# rgb-controller.net
KiCad netlist of a schematic drawn in EAGLE
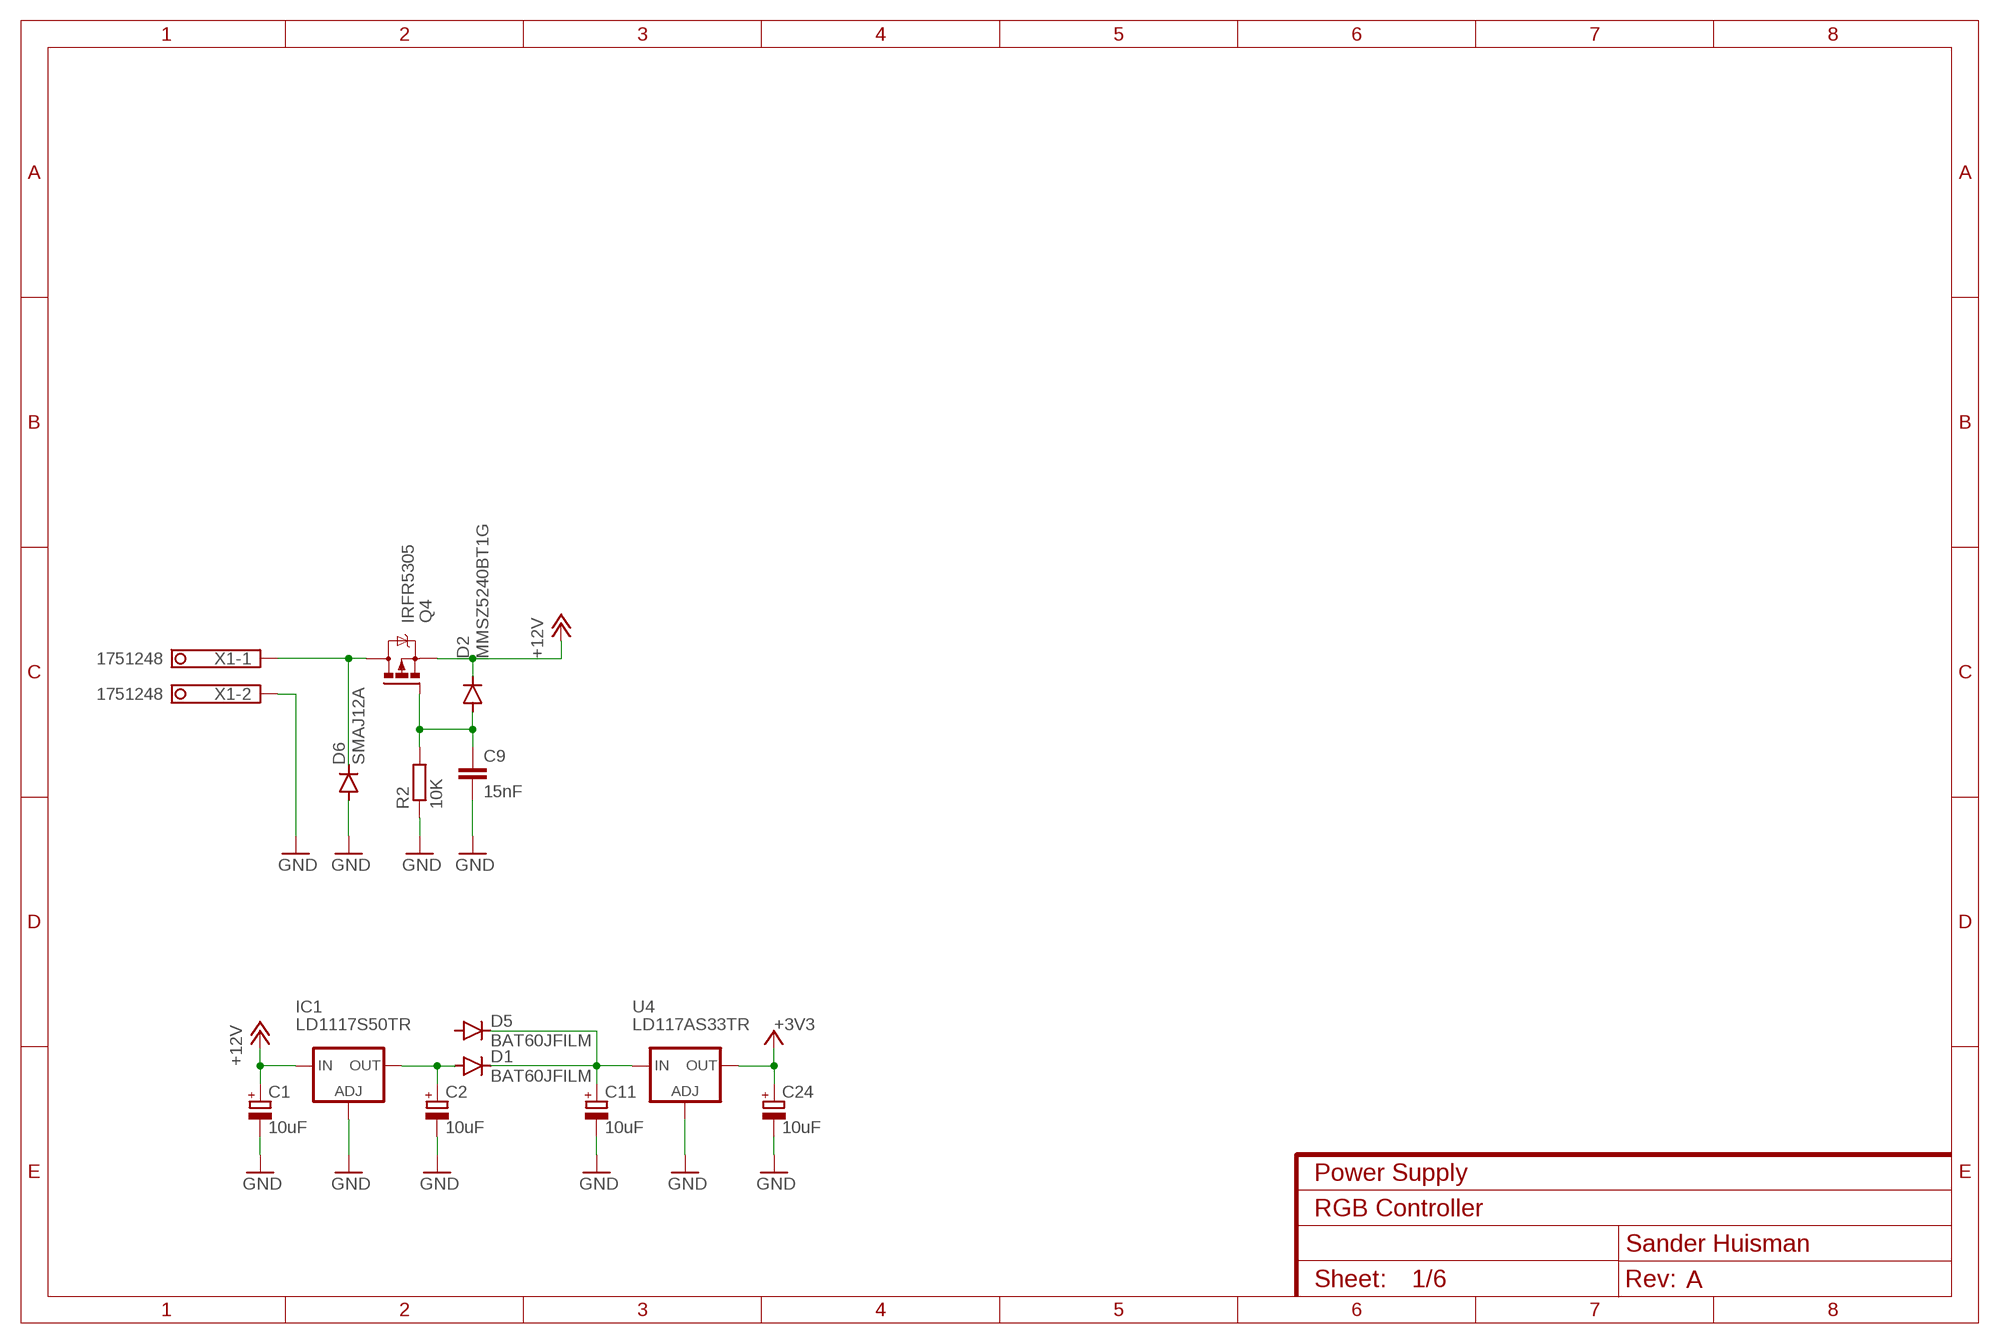
[diagram p0: schematic, sheet 1]
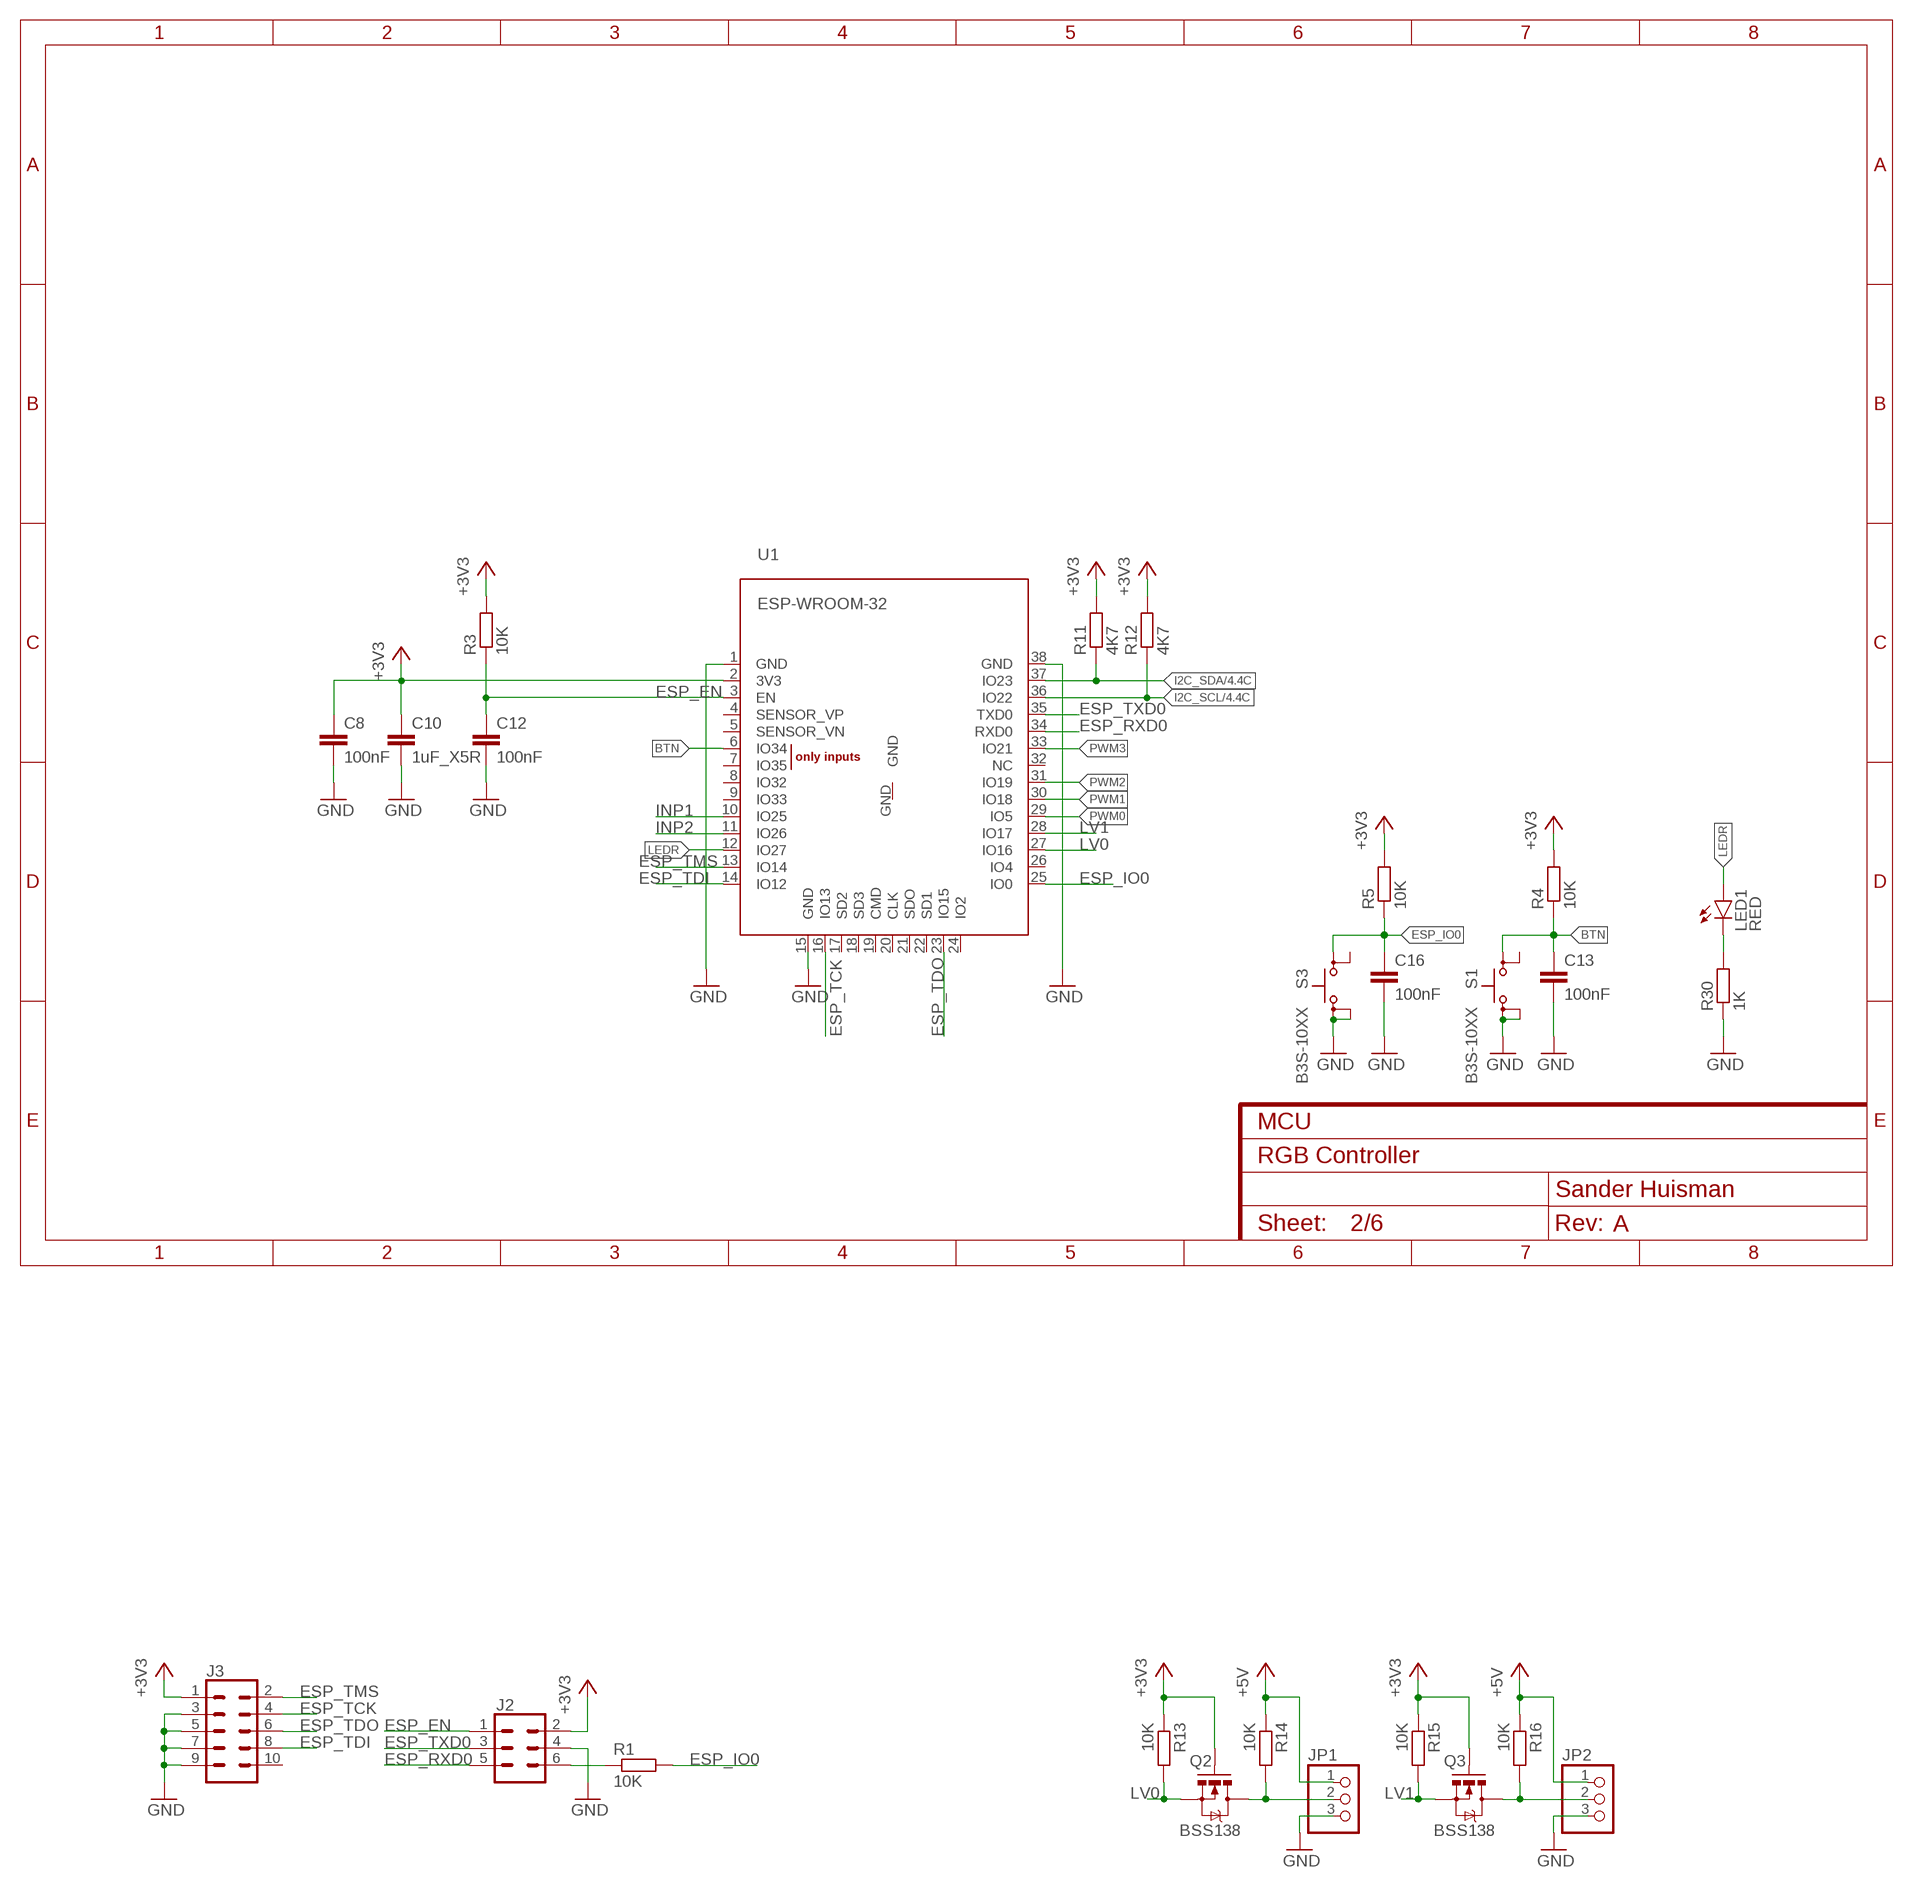
[diagram p1: schematic, sheet 2]
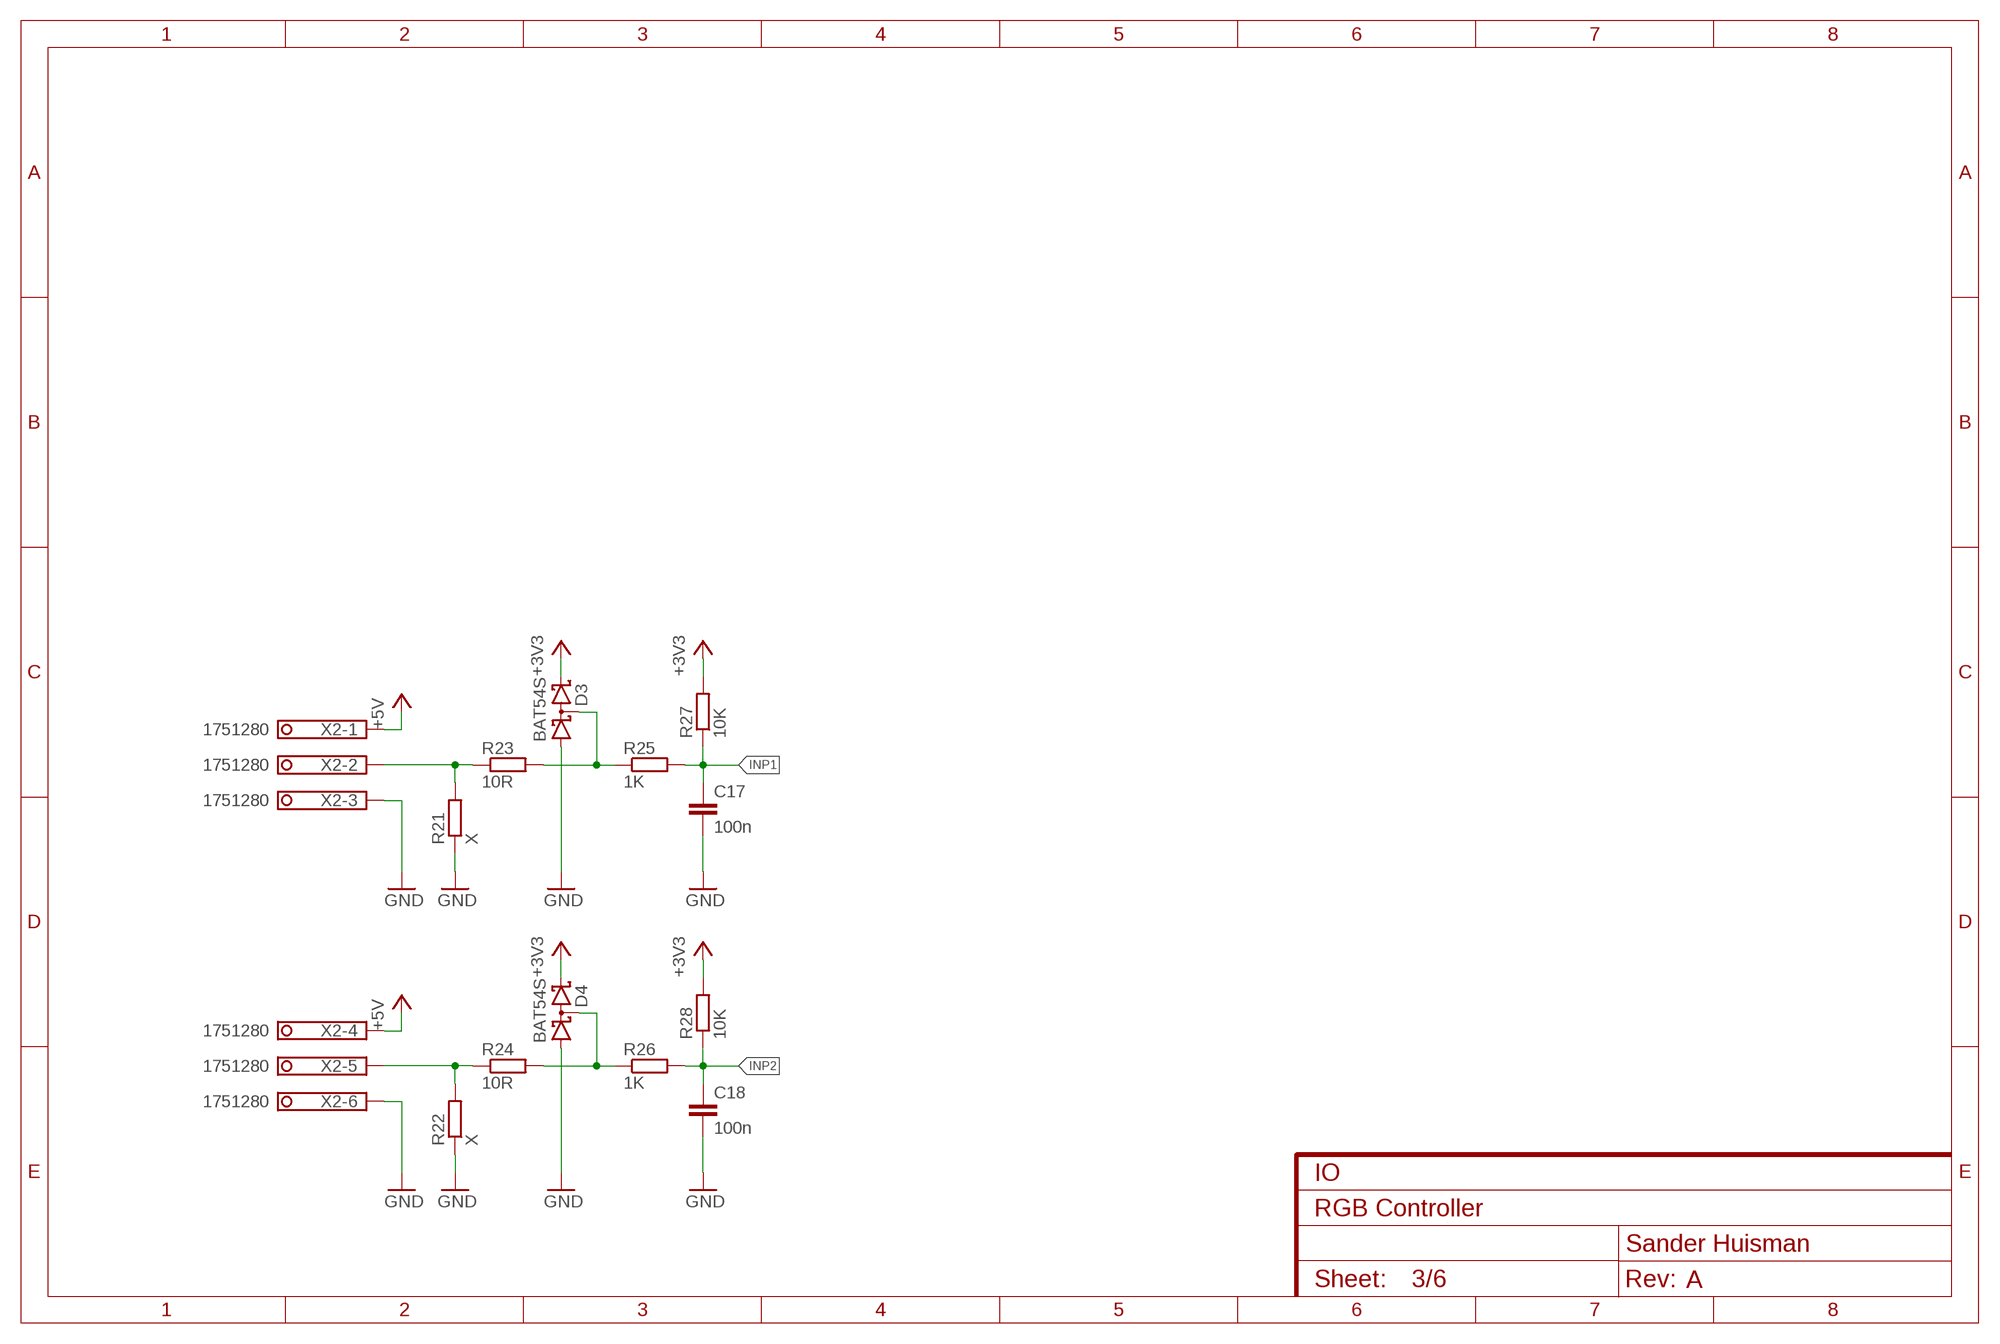
[diagram p2: schematic, sheet 3]
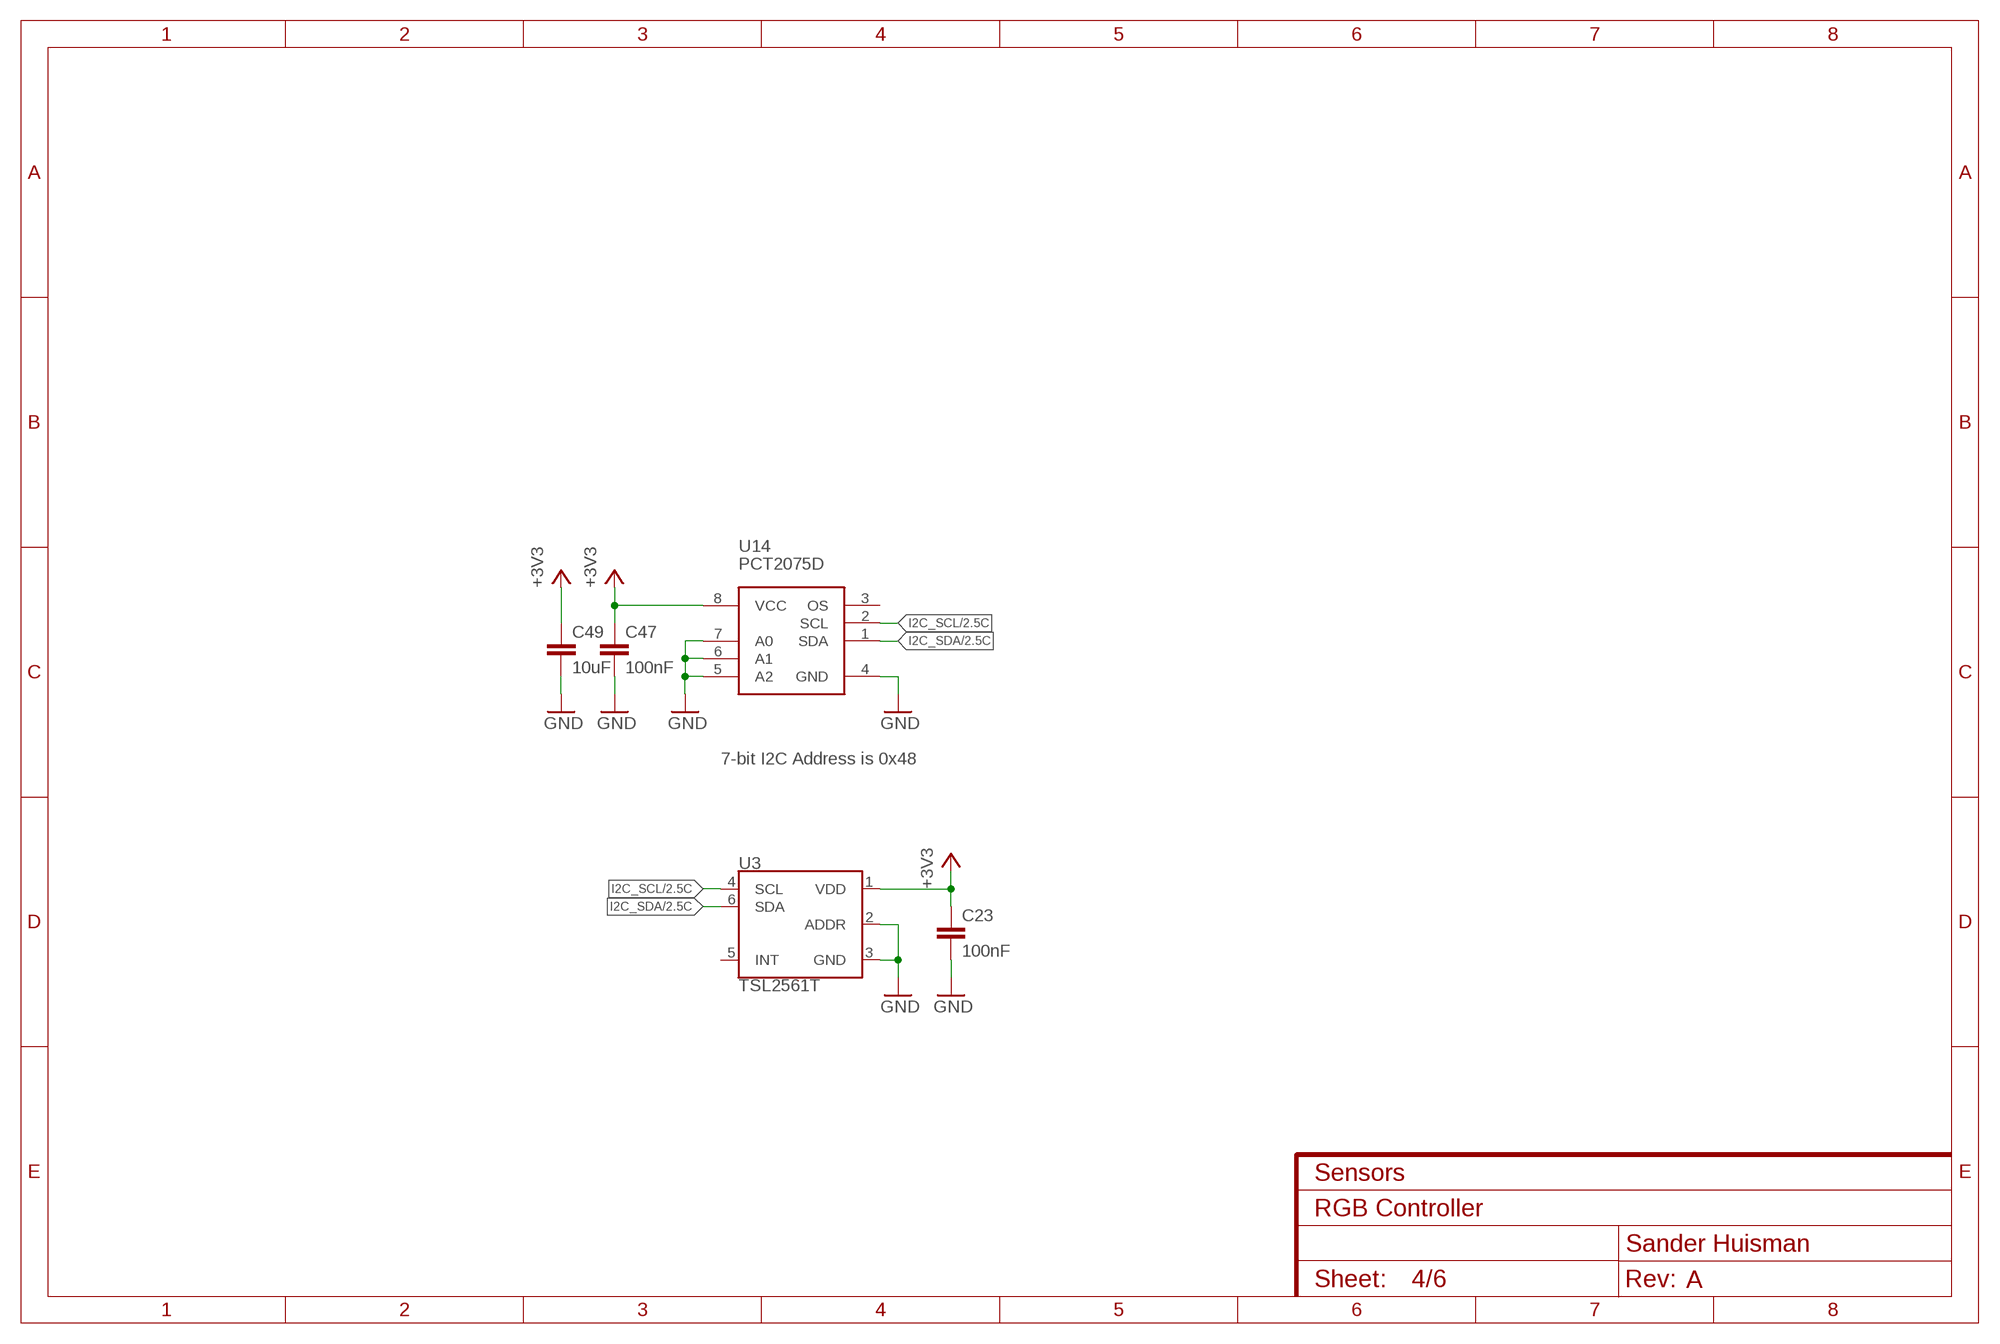
[diagram p3: schematic, sheet 4]
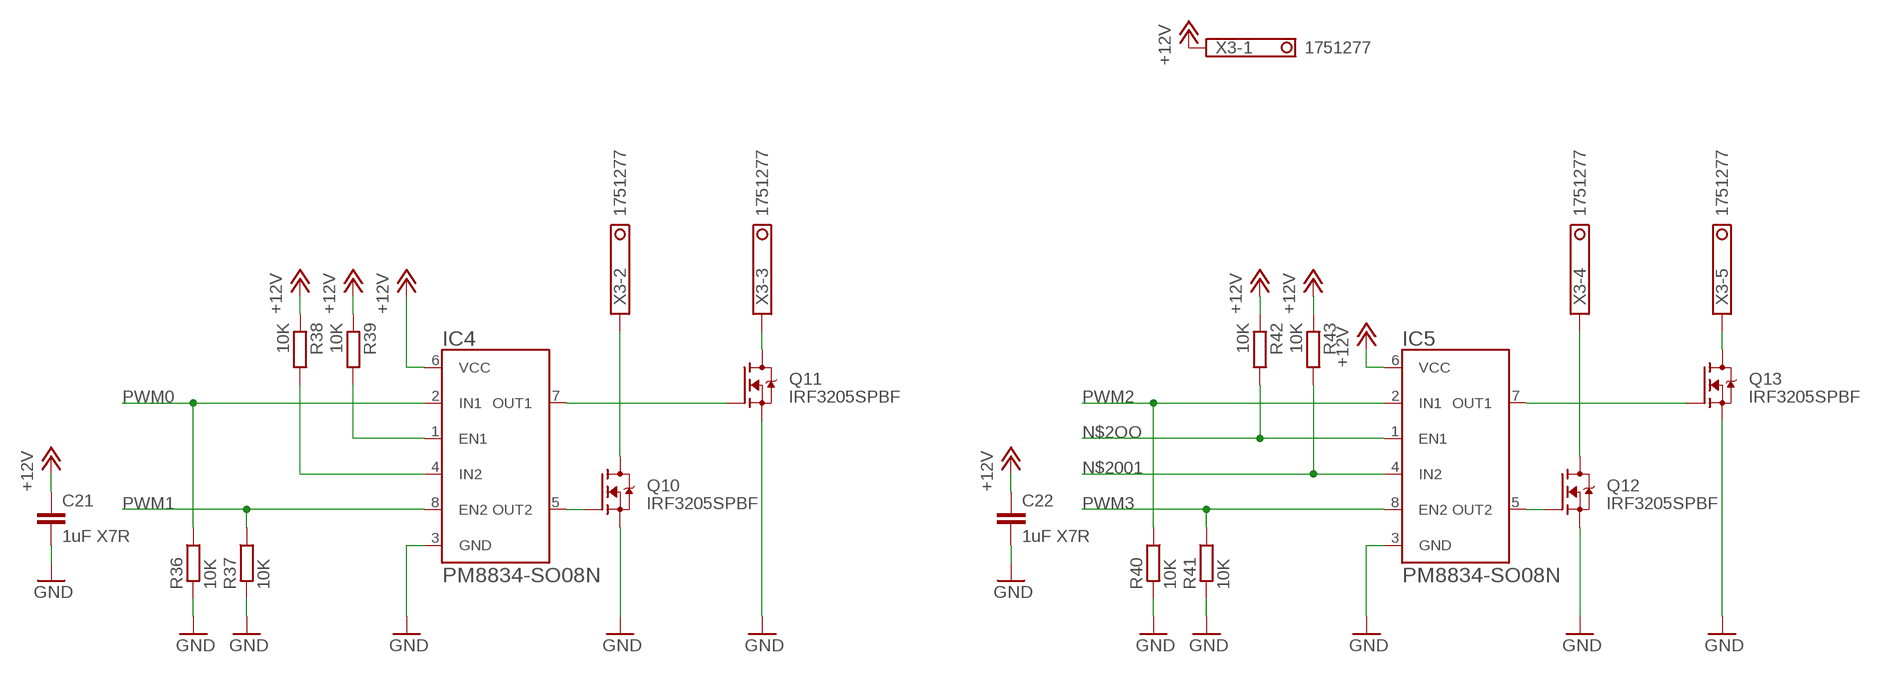
[diagram p4: schematic, sheet 5]
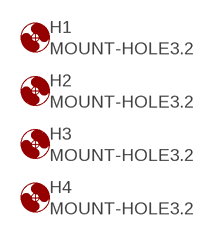
[diagram p5: schematic, sheet 6]

(export (version "E")
  (design (tool "Eeschema 10.0.6"))
  (components
    (comp (ref "C23")
      (value "100nF")
      (footprint "eagle-import:C0805")
      (libsource (lib "eagle-import") (part "C-EUC0805"))
    )
    (comp (ref "C47")
      (value "100nF")
      (footprint "eagle-import:C0805")
      (libsource (lib "eagle-import") (part "C-EUC0805"))
    )
    (comp (ref "C49")
      (value "10uF")
      (footprint "eagle-import:C0805")
      (libsource (lib "eagle-import") (part "C-EUC0805"))
    )
    (comp (ref "U3")
      (value "TSL2561T")
      (footprint "eagle-import:TMB-6")
      (libsource (lib "eagle-import") (part "TSL2561T"))
    )
    (comp (ref "U14")
      (value "PCT2075D")
      (footprint "eagle-import:SOIC8_150MIL")
      (libsource (lib "eagle-import") (part "PCT2075D"))
    )
    (comp (ref "C17")
      (value "100n")
      (footprint "eagle-import:C0805")
      (libsource (lib "eagle-import") (part "resistor_348_C-EUC0805"))
    )
    (comp (ref "C18")
      (value "100n")
      (footprint "eagle-import:C0805")
      (libsource (lib "eagle-import") (part "resistor_348_C-EUC0805"))
    )
    (comp (ref "D3")
      (value "BAT54S")
      (footprint "eagle-import:SOT23")
      (libsource (lib "eagle-import") (part "BAT54S"))
    )
    (comp (ref "D4")
      (value "BAT54S")
      (footprint "eagle-import:SOT23")
      (libsource (lib "eagle-import") (part "BAT54S"))
    )
    (comp (ref "R21")
      (value "X")
      (footprint "eagle-import:R0805")
      (libsource (lib "eagle-import") (part "resistor_348_R-EU_R0805"))
    )
    (comp (ref "R22")
      (value "X")
      (footprint "eagle-import:R0805")
      (libsource (lib "eagle-import") (part "resistor_348_R-EU_R0805"))
    )
    (comp (ref "R23")
      (value "10R")
      (footprint "eagle-import:R0805")
      (libsource (lib "eagle-import") (part "resistor_348_R-EU_R0805"))
    )
    (comp (ref "R24")
      (value "10R")
      (footprint "eagle-import:R0805")
      (libsource (lib "eagle-import") (part "resistor_348_R-EU_R0805"))
    )
    (comp (ref "R25")
      (value "1K")
      (footprint "eagle-import:R0805")
      (libsource (lib "eagle-import") (part "resistor_348_R-EU_R0805"))
    )
    (comp (ref "R26")
      (value "1K")
      (footprint "eagle-import:R0805")
      (libsource (lib "eagle-import") (part "resistor_348_R-EU_R0805"))
    )
    (comp (ref "R27")
      (value "10K")
      (footprint "eagle-import:R0805")
      (libsource (lib "eagle-import") (part "resistor_348_R-EU_R0805"))
    )
    (comp (ref "R28")
      (value "10K")
      (footprint "eagle-import:R0805")
      (libsource (lib "eagle-import") (part "resistor_348_R-EU_R0805"))
    )
    (comp (ref "X2")
      (value "1751280")
      (footprint "eagle-import:1751280")
      (libsource (lib "eagle-import") (part "1751280"))
    )
    (comp (ref "C8")
      (value "100nF")
      (footprint "eagle-import:C0805")
      (libsource (lib "eagle-import") (part "resistor_348_C-EUC0805"))
    )
    (comp (ref "C10")
      (value "1uF_X5R")
      (footprint "eagle-import:C0805")
      (libsource (lib "eagle-import") (part "resistor_348_C-EUC0805"))
    )
    (comp (ref "C12")
      (value "100nF")
      (footprint "eagle-import:C0805")
      (libsource (lib "eagle-import") (part "resistor_348_C-EUC0805"))
    )
    (comp (ref "C13")
      (value "100nF")
      (footprint "eagle-import:C0805")
      (libsource (lib "eagle-import") (part "resistor_348_C-EUC0805"))
    )
    (comp (ref "C16")
      (value "100nF")
      (footprint "eagle-import:C0805")
      (libsource (lib "eagle-import") (part "resistor_348_C-EUC0805"))
    )
    (comp (ref "J2")
      (value "CONN_03X2SHROUD")
      (footprint "eagle-import:2X3-SHROUDED")
      (libsource (lib "eagle-import") (part "CONN_03X2SHROUD"))
    )
    (comp (ref "J3")
      (value "CONN_05X2SHD")
      (footprint "eagle-import:2X5-SHROUDED")
      (libsource (lib "eagle-import") (part "CONN_05X2SHD"))
    )
    (comp (ref "JP1")
      (value "PINHD-1X3")
      (footprint "eagle-import:1X03")
      (libsource (lib "eagle-import") (part "PINHD-1X3"))
    )
    (comp (ref "JP2")
      (value "PINHD-1X3")
      (footprint "eagle-import:1X03")
      (libsource (lib "eagle-import") (part "PINHD-1X3"))
    )
    (comp (ref "LED1")
      (value "RED")
      (footprint "eagle-import:CHIPLED_0805")
      (libsource (lib "eagle-import") (part "LEDCHIPLED_0805"))
    )
    (comp (ref "Q2")
      (value "BSS138")
      (footprint "eagle-import:SOT23-3")
      (libsource (lib "eagle-import") (part "MOSFET-NCHANNELSMD"))
    )
    (comp (ref "Q3")
      (value "BSS138")
      (footprint "eagle-import:SOT23-3")
      (libsource (lib "eagle-import") (part "MOSFET-NCHANNELSMD"))
    )
    (comp (ref "R1")
      (value "10K")
      (footprint "eagle-import:R0805")
      (libsource (lib "eagle-import") (part "resistor_348_R-EU_R0805"))
    )
    (comp (ref "R3")
      (value "10K")
      (footprint "eagle-import:R0805")
      (libsource (lib "eagle-import") (part "R-EU_R0805"))
    )
    (comp (ref "R4")
      (value "10K")
      (footprint "eagle-import:R0805")
      (libsource (lib "eagle-import") (part "R-EU_R0805"))
    )
    (comp (ref "R5")
      (value "10K")
      (footprint "eagle-import:R0805")
      (libsource (lib "eagle-import") (part "R-EU_R0805"))
    )
    (comp (ref "R11")
      (value "4K7")
      (footprint "eagle-import:R0805")
      (libsource (lib "eagle-import") (part "resistor_348_R-EU_R0805"))
    )
    (comp (ref "R12")
      (value "4K7")
      (footprint "eagle-import:R0805")
      (libsource (lib "eagle-import") (part "resistor_348_R-EU_R0805"))
    )
    (comp (ref "R13")
      (value "10K")
      (footprint "eagle-import:R0805")
      (libsource (lib "eagle-import") (part "resistor_348_R-EU_R0805"))
    )
    (comp (ref "R14")
      (value "10K")
      (footprint "eagle-import:R0805")
      (libsource (lib "eagle-import") (part "resistor_348_R-EU_R0805"))
    )
    (comp (ref "R15")
      (value "10K")
      (footprint "eagle-import:R0805")
      (libsource (lib "eagle-import") (part "resistor_348_R-EU_R0805"))
    )
    (comp (ref "R16")
      (value "10K")
      (footprint "eagle-import:R0805")
      (libsource (lib "eagle-import") (part "resistor_348_R-EU_R0805"))
    )
    (comp (ref "R30")
      (value "1K")
      (footprint "eagle-import:R0805")
      (libsource (lib "eagle-import") (part "resistor_348_R-EU_R0805"))
    )
    (comp (ref "S1")
      (value "B3S-10XX")
      (footprint "eagle-import:B3S-10XX")
      (libsource (lib "eagle-import") (part "B3S-10XX"))
    )
    (comp (ref "S3")
      (value "B3S-10XX")
      (footprint "eagle-import:B3S-10XX")
      (libsource (lib "eagle-import") (part "B3S-10XX"))
    )
    (comp (ref "U1")
      (value "ESP-WROOM-32")
      (footprint "eagle-import:ESP-WROOM-32")
      (libsource (lib "eagle-import") (part "ESP-WROOM-32"))
    )
    (comp (ref "C21")
      (value "1uF X7R")
      (footprint "eagle-import:C0805")
      (libsource (lib "eagle-import") (part "resistor_348_C-EUC0805"))
    )
    (comp (ref "C22")
      (value "1uF X7R")
      (footprint "eagle-import:C0805")
      (libsource (lib "eagle-import") (part "resistor_348_C-EUC0805"))
    )
    (comp (ref "IC4")
      (value "PM8834-SO08N")
      (footprint "eagle-import:SO08N")
      (fields (field (name "MF") "STMicroelectronics") (field (name "MP") "PM8834"))
      (libsource (lib "eagle-import") (part "PM8834-SO08N"))
    )
    (comp (ref "IC5")
      (value "PM8834-SO08N")
      (footprint "eagle-import:SO08N")
      (fields (field (name "MF") "STMicroelectronics") (field (name "MP") "PM8834"))
      (libsource (lib "eagle-import") (part "PM8834-SO08N"))
    )
    (comp (ref "Q10")
      (value "IRF3205SPBF")
      (footprint "eagle-import:TRANS_IRF3205SPBF")
      (fields (field (name "MF") "Infineon Technologies"))
      (libsource (lib "eagle-import") (part "IRF3205SPBF"))
    )
    (comp (ref "Q11")
      (value "IRF3205SPBF")
      (footprint "eagle-import:TRANS_IRF3205SPBF")
      (fields (field (name "MF") "Infineon Technologies"))
      (libsource (lib "eagle-import") (part "IRF3205SPBF"))
    )
    (comp (ref "Q12")
      (value "IRF3205SPBF")
      (footprint "eagle-import:TRANS_IRF3205SPBF")
      (fields (field (name "MF") "Infineon Technologies"))
      (libsource (lib "eagle-import") (part "IRF3205SPBF"))
    )
    (comp (ref "Q13")
      (value "IRF3205SPBF")
      (footprint "eagle-import:TRANS_IRF3205SPBF")
      (fields (field (name "MF") "Infineon Technologies"))
      (libsource (lib "eagle-import") (part "IRF3205SPBF"))
    )
    (comp (ref "R36")
      (value "10K")
      (footprint "eagle-import:R0805")
      (libsource (lib "eagle-import") (part "resistor_348_R-EU_R0805"))
    )
    (comp (ref "R37")
      (value "10K")
      (footprint "eagle-import:R0805")
      (libsource (lib "eagle-import") (part "resistor_348_R-EU_R0805"))
    )
    (comp (ref "R38")
      (value "10K")
      (footprint "eagle-import:R0805")
      (libsource (lib "eagle-import") (part "resistor_348_R-EU_R0805"))
    )
    (comp (ref "R39")
      (value "10K")
      (footprint "eagle-import:R0805")
      (libsource (lib "eagle-import") (part "resistor_348_R-EU_R0805"))
    )
    (comp (ref "R40")
      (value "10K")
      (footprint "eagle-import:R0805")
      (libsource (lib "eagle-import") (part "resistor_348_R-EU_R0805"))
    )
    (comp (ref "R41")
      (value "10K")
      (footprint "eagle-import:R0805")
      (libsource (lib "eagle-import") (part "resistor_348_R-EU_R0805"))
    )
    (comp (ref "R42")
      (value "10K")
      (footprint "eagle-import:R0805")
      (libsource (lib "eagle-import") (part "resistor_348_R-EU_R0805"))
    )
    (comp (ref "R43")
      (value "10K")
      (footprint "eagle-import:R0805")
      (libsource (lib "eagle-import") (part "resistor_348_R-EU_R0805"))
    )
    (comp (ref "X3")
      (value "1751277")
      (footprint "eagle-import:1751277")
      (libsource (lib "eagle-import") (part "1751277"))
    )
    (comp (ref "C1")
      (value "10uF")
      (footprint "eagle-import:SMC_C")
      (libsource (lib "eagle-import") (part "CPOL-EUSMCC"))
    )
    (comp (ref "C2")
      (value "10uF")
      (footprint "eagle-import:SMC_C")
      (libsource (lib "eagle-import") (part "CPOL-EUSMCC"))
    )
    (comp (ref "C9")
      (value "15nF")
      (footprint "eagle-import:C0805")
      (libsource (lib "eagle-import") (part "resistor_348_C-EUC0805"))
    )
    (comp (ref "C11")
      (value "10uF")
      (footprint "eagle-import:SMC_C")
      (libsource (lib "eagle-import") (part "CPOL-EUSMCC"))
    )
    (comp (ref "C24")
      (value "10uF")
      (footprint "eagle-import:SMC_C")
      (libsource (lib "eagle-import") (part "CPOL-EUSMCC"))
    )
    (comp (ref "D1")
      (value "BAT60JFILM")
      (footprint "eagle-import:SOD323-W")
      (libsource (lib "eagle-import") (part "DIODE-SOD323-W"))
    )
    (comp (ref "D2")
      (value "MMSZ5240BT1G")
      (footprint "eagle-import:SOD123")
      (libsource (lib "eagle-import") (part "DIODE-SOD123"))
    )
    (comp (ref "D5")
      (value "BAT60JFILM")
      (footprint "eagle-import:SOD323-W")
      (libsource (lib "eagle-import") (part "DIODE-SOD323-W"))
    )
    (comp (ref "D6")
      (value "SMAJ12A")
      (footprint "eagle-import:DO-214AC")
      (libsource (lib "eagle-import") (part "DIODE-DO-214AC"))
    )
    (comp (ref "IC1")
      (value "LD1117S50TR")
      (footprint "eagle-import:SOT223")
      (libsource (lib "eagle-import") (part "LD117A?S50TR"))
    )
    (comp (ref "Q4")
      (value "IRFR5305")
      (footprint "eagle-import:D-PAK_TO252AA")
      (libsource (lib "eagle-import") (part "IRF?5305R"))
    )
    (comp (ref "R2")
      (value "10K")
      (footprint "eagle-import:R0805")
      (libsource (lib "eagle-import") (part "R-EU_R0805"))
    )
    (comp (ref "U4")
      (value "LD117AS33TR")
      (footprint "eagle-import:SOT223")
      (libsource (lib "eagle-import") (part "LD117A?S33TR"))
    )
    (comp (ref "X1")
      (value "1751248")
      (footprint "eagle-import:1751248")
      (libsource (lib "eagle-import") (part "1751248"))
    )
    (comp (ref "H1")
      (value "MOUNT-HOLE3.2")
      (footprint "eagle-import:3,2")
      (libsource (lib "eagle-import") (part "MOUNT-HOLE3.2"))
    )
    (comp (ref "H2")
      (value "MOUNT-HOLE3.2")
      (footprint "eagle-import:3,2")
      (libsource (lib "eagle-import") (part "MOUNT-HOLE3.2"))
    )
    (comp (ref "H3")
      (value "MOUNT-HOLE3.2")
      (footprint "eagle-import:3,2")
      (libsource (lib "eagle-import") (part "MOUNT-HOLE3.2"))
    )
    (comp (ref "H4")
      (value "MOUNT-HOLE3.2")
      (footprint "eagle-import:3,2")
      (libsource (lib "eagle-import") (part "MOUNT-HOLE3.2"))
    )
  )
  (nets
    (net (code "1") (name "+3V3") (class "Default")
      (node (ref "C10") (pin "1") (pinfunction "1_1") (pintype "passive"))
      (node (ref "C23") (pin "1") (pinfunction "1_1") (pintype "passive"))
      (node (ref "C24") (pin "+") (pinfunction "+_+") (pintype "passive"))
      (node (ref "C47") (pin "1") (pinfunction "1_1") (pintype "passive"))
      (node (ref "C49") (pin "1") (pinfunction "1_1") (pintype "passive"))
      (node (ref "C8") (pin "1") (pinfunction "1_1") (pintype "passive"))
      (node (ref "D3") (pin "2") (pinfunction "C2_2") (pintype "passive"))
      (node (ref "D4") (pin "2") (pinfunction "C2_2") (pintype "passive"))
      (node (ref "J2") (pin "2") (pinfunction "2_2") (pintype "bidirectional"))
      (node (ref "J3") (pin "1") (pinfunction "1_1") (pintype "passive"))
      (node (ref "Q2") (pin "1") (pinfunction "G_1") (pintype "passive"))
      (node (ref "Q3") (pin "1") (pinfunction "G_1") (pintype "passive"))
      (node (ref "R11") (pin "2") (pinfunction "2_2") (pintype "passive"))
      (node (ref "R12") (pin "2") (pinfunction "2_2") (pintype "passive"))
      (node (ref "R13") (pin "1") (pinfunction "1_1") (pintype "passive"))
      (node (ref "R15") (pin "1") (pinfunction "1_1") (pintype "passive"))
      (node (ref "R27") (pin "2") (pinfunction "2_2") (pintype "passive"))
      (node (ref "R28") (pin "2") (pinfunction "2_2") (pintype "passive"))
      (node (ref "R3") (pin "2") (pinfunction "2_2") (pintype "passive"))
      (node (ref "R4") (pin "2") (pinfunction "2_2") (pintype "passive"))
      (node (ref "R5") (pin "2") (pinfunction "2_2") (pintype "passive"))
      (node (ref "U1") (pin "2") (pinfunction "3V3_2") (pintype "bidirectional"))
      (node (ref "U14") (pin "8") (pinfunction "VCC_8") (pintype "power_in"))
      (node (ref "U3") (pin "1") (pinfunction "VDD_1") (pintype "power_in"))
      (node (ref "U4") (pin "4") (pinfunction "OUT_4") (pintype "passive"))
    )
    (net (code "2") (name "+5V") (class "Default")
      (node (ref "JP1") (pin "1") (pinfunction "1_1") (pintype "passive"))
      (node (ref "JP2") (pin "1") (pinfunction "1_1") (pintype "passive"))
      (node (ref "R14") (pin "1") (pinfunction "1_1") (pintype "passive"))
      (node (ref "R16") (pin "1") (pinfunction "1_1") (pintype "passive"))
      (node (ref "X2") (pin "1") (pinfunction "K_1") (pintype "passive"))
      (node (ref "X2") (pin "4") (pinfunction "K_4") (pintype "passive"))
    )
    (net (code "3") (name "+12V") (class "Default")
      (node (ref "C1") (pin "+") (pinfunction "+_+") (pintype "passive"))
      (node (ref "C21") (pin "1") (pinfunction "1_1") (pintype "passive"))
      (node (ref "C22") (pin "1") (pinfunction "1_1") (pintype "passive"))
      (node (ref "D2") (pin "C") (pinfunction "C_C") (pintype "passive"))
      (node (ref "IC1") (pin "3") (pinfunction "IN_3") (pintype "input"))
      (node (ref "IC4") (pin "6") (pinfunction "VCC_6") (pintype "power_in"))
      (node (ref "IC5") (pin "6") (pinfunction "VCC_6") (pintype "power_in"))
      (node (ref "Q4") (pin "3") (pinfunction "S_3") (pintype "passive"))
      (node (ref "R38") (pin "2") (pinfunction "2_2") (pintype "passive"))
      (node (ref "R39") (pin "2") (pinfunction "2_2") (pintype "passive"))
      (node (ref "R42") (pin "2") (pinfunction "2_2") (pintype "passive"))
      (node (ref "R43") (pin "2") (pinfunction "2_2") (pintype "passive"))
      (node (ref "X3") (pin "1") (pinfunction "K_1") (pintype "passive"))
    )
    (net (code "4") (name "BTN") (class "Default")
      (node (ref "C13") (pin "1") (pinfunction "1_1") (pintype "passive"))
      (node (ref "R4") (pin "1") (pinfunction "1_1") (pintype "passive"))
      (node (ref "S1") (pin "1") (pinfunction "P_1") (pintype "passive"))
      (node (ref "U1") (pin "6") (pinfunction "IO34_6") (pintype "input"))
    )
    (net (code "5") (name "ESP_EN") (class "Default")
      (node (ref "C12") (pin "1") (pinfunction "1_1") (pintype "passive"))
      (node (ref "J2") (pin "1") (pinfunction "1_1") (pintype "bidirectional"))
      (node (ref "R3") (pin "1") (pinfunction "1_1") (pintype "passive"))
      (node (ref "U1") (pin "3") (pinfunction "EN_3") (pintype "bidirectional"))
    )
    (net (code "6") (name "ESP_IO0") (class "Default")
      (node (ref "C16") (pin "1") (pinfunction "1_1") (pintype "passive"))
      (node (ref "R1") (pin "2") (pinfunction "2_2") (pintype "passive"))
      (node (ref "R5") (pin "1") (pinfunction "1_1") (pintype "passive"))
      (node (ref "S3") (pin "1") (pinfunction "P_1") (pintype "passive"))
      (node (ref "U1") (pin "25") (pinfunction "IO0_25") (pintype "bidirectional"))
    )
    (net (code "7") (name "ESP_RXD0") (class "Default")
      (node (ref "J2") (pin "5") (pinfunction "5_5") (pintype "bidirectional"))
      (node (ref "U1") (pin "34") (pinfunction "RXD0_34") (pintype "bidirectional"))
    )
    (net (code "8") (name "ESP_TCK") (class "Default")
      (node (ref "J3") (pin "4") (pinfunction "4_4") (pintype "passive"))
      (node (ref "U1") (pin "16") (pinfunction "IO13_16") (pintype "bidirectional"))
    )
    (net (code "9") (name "ESP_TDI") (class "Default")
      (node (ref "J3") (pin "8") (pinfunction "8_8") (pintype "passive"))
      (node (ref "U1") (pin "14") (pinfunction "IO12_14") (pintype "bidirectional"))
    )
    (net (code "10") (name "ESP_TDO") (class "Default")
      (node (ref "J3") (pin "6") (pinfunction "6_6") (pintype "passive"))
      (node (ref "U1") (pin "23") (pinfunction "IO15_23") (pintype "bidirectional"))
    )
    (net (code "11") (name "ESP_TMS") (class "Default")
      (node (ref "J3") (pin "2") (pinfunction "2_2") (pintype "passive"))
      (node (ref "U1") (pin "13") (pinfunction "IO14_13") (pintype "bidirectional"))
    )
    (net (code "12") (name "ESP_TXD0") (class "Default")
      (node (ref "J2") (pin "3") (pinfunction "3_3") (pintype "bidirectional"))
      (node (ref "U1") (pin "35") (pinfunction "TXD0_35") (pintype "bidirectional"))
    )
    (net (code "13") (name "GND") (class "Default")
      (node (ref "C1") (pin "-") (pinfunction "-_-") (pintype "passive"))
      (node (ref "C10") (pin "2") (pinfunction "2_2") (pintype "passive"))
      (node (ref "C11") (pin "-") (pinfunction "-_-") (pintype "passive"))
      (node (ref "C12") (pin "2") (pinfunction "2_2") (pintype "passive"))
      (node (ref "C13") (pin "2") (pinfunction "2_2") (pintype "passive"))
      (node (ref "C16") (pin "2") (pinfunction "2_2") (pintype "passive"))
      (node (ref "C17") (pin "2") (pinfunction "2_2") (pintype "passive"))
      (node (ref "C18") (pin "2") (pinfunction "2_2") (pintype "passive"))
      (node (ref "C2") (pin "-") (pinfunction "-_-") (pintype "passive"))
      (node (ref "C21") (pin "2") (pinfunction "2_2") (pintype "passive"))
      (node (ref "C22") (pin "2") (pinfunction "2_2") (pintype "passive"))
      (node (ref "C23") (pin "2") (pinfunction "2_2") (pintype "passive"))
      (node (ref "C24") (pin "-") (pinfunction "-_-") (pintype "passive"))
      (node (ref "C47") (pin "2") (pinfunction "2_2") (pintype "passive"))
      (node (ref "C49") (pin "2") (pinfunction "2_2") (pintype "passive"))
      (node (ref "C8") (pin "2") (pinfunction "2_2") (pintype "passive"))
      (node (ref "C9") (pin "2") (pinfunction "2_2") (pintype "passive"))
      (node (ref "D3") (pin "1") (pinfunction "A1_1") (pintype "passive"))
      (node (ref "D4") (pin "1") (pinfunction "A1_1") (pintype "passive"))
      (node (ref "D6") (pin "A") (pinfunction "A_A") (pintype "passive"))
      (node (ref "IC1") (pin "1") (pinfunction "ADJ_1") (pintype "input"))
      (node (ref "IC4") (pin "3") (pinfunction "GND_3") (pintype "power_in"))
      (node (ref "IC5") (pin "3") (pinfunction "GND_3") (pintype "power_in"))
      (node (ref "J2") (pin "4") (pinfunction "4_4") (pintype "bidirectional"))
      (node (ref "J3") (pin "3") (pinfunction "3_3") (pintype "passive"))
      (node (ref "J3") (pin "5") (pinfunction "5_5") (pintype "passive"))
      (node (ref "J3") (pin "7") (pinfunction "7_7") (pintype "passive"))
      (node (ref "J3") (pin "9") (pinfunction "9_9") (pintype "passive"))
      (node (ref "JP1") (pin "3") (pinfunction "3_3") (pintype "passive"))
      (node (ref "JP2") (pin "3") (pinfunction "3_3") (pintype "passive"))
      (node (ref "Q10") (pin "3") (pinfunction "S_3") (pintype "passive"))
      (node (ref "Q11") (pin "3") (pinfunction "S_3") (pintype "passive"))
      (node (ref "Q12") (pin "3") (pinfunction "S_3") (pintype "passive"))
      (node (ref "Q13") (pin "3") (pinfunction "S_3") (pintype "passive"))
      (node (ref "R2") (pin "1") (pinfunction "1_1") (pintype "passive"))
      (node (ref "R21") (pin "1") (pinfunction "1_1") (pintype "passive"))
      (node (ref "R22") (pin "1") (pinfunction "1_1") (pintype "passive"))
      (node (ref "R30") (pin "2") (pinfunction "2_2") (pintype "passive"))
      (node (ref "R36") (pin "2") (pinfunction "2_2") (pintype "passive"))
      (node (ref "R37") (pin "2") (pinfunction "2_2") (pintype "passive"))
      (node (ref "R40") (pin "2") (pinfunction "2_2") (pintype "passive"))
      (node (ref "R41") (pin "2") (pinfunction "2_2") (pintype "passive"))
      (node (ref "S1") (pin "3") (pinfunction "S_3") (pintype "passive"))
      (node (ref "S1") (pin "4") (pinfunction "S1_4") (pintype "passive"))
      (node (ref "S3") (pin "3") (pinfunction "S_3") (pintype "passive"))
      (node (ref "S3") (pin "4") (pinfunction "S1_4") (pintype "passive"))
      (node (ref "U1") (pin "1") (pinfunction "GND_1") (pintype "bidirectional"))
      (node (ref "U1") (pin "15") (pinfunction "GND_15") (pintype "bidirectional"))
      (node (ref "U1") (pin "38") (pinfunction "GND_38") (pintype "bidirectional"))
      (node (ref "U14") (pin "4") (pinfunction "GND_4") (pintype "power_in"))
      (node (ref "U14") (pin "5") (pinfunction "A2_5") (pintype "input"))
      (node (ref "U14") (pin "6") (pinfunction "A1_6") (pintype "input"))
      (node (ref "U14") (pin "7") (pinfunction "A0_7") (pintype "input"))
      (node (ref "U3") (pin "2") (pinfunction "ADDR_2") (pintype "input"))
      (node (ref "U3") (pin "3") (pinfunction "GND_3") (pintype "power_in"))
      (node (ref "U4") (pin "1") (pinfunction "ADJ_1") (pintype "input"))
      (node (ref "X1") (pin "2") (pinfunction "K_2") (pintype "passive"))
      (node (ref "X2") (pin "3") (pinfunction "K_3") (pintype "passive"))
      (node (ref "X2") (pin "6") (pinfunction "K_6") (pintype "passive"))
    )
    (net (code "14") (name "I2C_SCL") (class "Default")
      (node (ref "R12") (pin "1") (pinfunction "1_1") (pintype "passive"))
      (node (ref "U1") (pin "36") (pinfunction "IO22_36") (pintype "bidirectional"))
      (node (ref "U14") (pin "2") (pinfunction "SCL_2") (pintype "bidirectional"))
      (node (ref "U3") (pin "4") (pinfunction "SCL_4") (pintype "input"))
    )
    (net (code "15") (name "I2C_SDA") (class "Default")
      (node (ref "R11") (pin "1") (pinfunction "1_1") (pintype "passive"))
      (node (ref "U1") (pin "37") (pinfunction "IO23_37") (pintype "bidirectional"))
      (node (ref "U14") (pin "1") (pinfunction "SDA_1") (pintype "bidirectional"))
      (node (ref "U3") (pin "6") (pinfunction "SDA_6") (pintype "bidirectional"))
    )
    (net (code "16") (name "INP1") (class "Default")
      (node (ref "C17") (pin "1") (pinfunction "1_1") (pintype "passive"))
      (node (ref "R25") (pin "2") (pinfunction "2_2") (pintype "passive"))
      (node (ref "R27") (pin "1") (pinfunction "1_1") (pintype "passive"))
      (node (ref "U1") (pin "10") (pinfunction "IO25_10") (pintype "bidirectional"))
    )
    (net (code "17") (name "INP2") (class "Default")
      (node (ref "C18") (pin "1") (pinfunction "1_1") (pintype "passive"))
      (node (ref "R26") (pin "2") (pinfunction "2_2") (pintype "passive"))
      (node (ref "R28") (pin "1") (pinfunction "1_1") (pintype "passive"))
      (node (ref "U1") (pin "11") (pinfunction "IO26_11") (pintype "bidirectional"))
    )
    (net (code "18") (name "LEDR") (class "Default")
      (node (ref "LED1") (pin "A") (pinfunction "A_A") (pintype "passive"))
      (node (ref "U1") (pin "12") (pinfunction "IO27_12") (pintype "bidirectional"))
    )
    (net (code "19") (name "LV0") (class "Default")
      (node (ref "Q2") (pin "2") (pinfunction "S_2") (pintype "passive"))
      (node (ref "R13") (pin "2") (pinfunction "2_2") (pintype "passive"))
      (node (ref "U1") (pin "27") (pinfunction "IO16_27") (pintype "bidirectional"))
    )
    (net (code "20") (name "LV1") (class "Default")
      (node (ref "Q3") (pin "2") (pinfunction "S_2") (pintype "passive"))
      (node (ref "R15") (pin "2") (pinfunction "2_2") (pintype "passive"))
      (node (ref "U1") (pin "28") (pinfunction "IO17_28") (pintype "bidirectional"))
    )
    (net (code "21") (name "N$2OO") (class "Default")
      (node (ref "IC5") (pin "1") (pinfunction "EN1_1") (pintype "input"))
      (node (ref "R42") (pin "1") (pinfunction "1_1") (pintype "passive"))
    )
    (net (code "22") (name "N$2001") (class "Default")
      (node (ref "IC5") (pin "4") (pinfunction "IN2_4") (pintype "input"))
      (node (ref "R43") (pin "1") (pinfunction "1_1") (pintype "passive"))
    )
    (net (code "23") (name "Net-(D3-C1A2)") (class "Default")
      (node (ref "D3") (pin "3") (pinfunction "C1A2_3") (pintype "passive"))
      (node (ref "R23") (pin "2") (pinfunction "2_2") (pintype "passive"))
      (node (ref "R25") (pin "1") (pinfunction "1_1") (pintype "passive"))
    )
    (net (code "24") (name "Net-(D4-C1A2)") (class "Default")
      (node (ref "D4") (pin "3") (pinfunction "C1A2_3") (pintype "passive"))
      (node (ref "R24") (pin "2") (pinfunction "2_2") (pintype "passive"))
      (node (ref "R26") (pin "1") (pinfunction "1_1") (pintype "passive"))
    )
    (net (code "25") (name "Net-(IC1-OUT)") (class "Default")
      (node (ref "C2") (pin "+") (pinfunction "+_+") (pintype "passive"))
      (node (ref "D1") (pin "A") (pinfunction "A_A") (pintype "passive"))
      (node (ref "IC1") (pin "4") (pinfunction "OUT_4") (pintype "passive"))
    )
    (net (code "26") (name "Net-(IC4-EN1)") (class "Default")
      (node (ref "IC4") (pin "1") (pinfunction "EN1_1") (pintype "input"))
      (node (ref "R39") (pin "1") (pinfunction "1_1") (pintype "passive"))
    )
    (net (code "27") (name "Net-(IC4-IN2)") (class "Default")
      (node (ref "IC4") (pin "4") (pinfunction "IN2_4") (pintype "input"))
      (node (ref "R38") (pin "1") (pinfunction "1_1") (pintype "passive"))
    )
    (net (code "28") (name "Net-(IC4-OUT1)") (class "Default")
      (node (ref "IC4") (pin "7") (pinfunction "OUT1_7") (pintype "bidirectional"))
      (node (ref "Q11") (pin "1") (pinfunction "G_1") (pintype "passive"))
    )
    (net (code "29") (name "Net-(IC4-OUT2)") (class "Default")
      (node (ref "IC4") (pin "5") (pinfunction "OUT2_5") (pintype "bidirectional"))
      (node (ref "Q10") (pin "1") (pinfunction "G_1") (pintype "passive"))
    )
    (net (code "30") (name "Net-(IC5-OUT1)") (class "Default")
      (node (ref "IC5") (pin "7") (pinfunction "OUT1_7") (pintype "bidirectional"))
      (node (ref "Q13") (pin "1") (pinfunction "G_1") (pintype "passive"))
    )
    (net (code "31") (name "Net-(IC5-OUT2)") (class "Default")
      (node (ref "IC5") (pin "5") (pinfunction "OUT2_5") (pintype "bidirectional"))
      (node (ref "Q12") (pin "1") (pinfunction "G_1") (pintype "passive"))
    )
    (net (code "32") (name "Net-(J2-Pad6)") (class "Default")
      (node (ref "J2") (pin "6") (pinfunction "6_6") (pintype "bidirectional"))
      (node (ref "R1") (pin "1") (pinfunction "1_1") (pintype "passive"))
    )
    (net (code "33") (name "Net-(LED1-PadC)") (class "Default")
      (node (ref "LED1") (pin "C") (pinfunction "C_C") (pintype "passive"))
      (node (ref "R30") (pin "1") (pinfunction "1_1") (pintype "passive"))
    )
    (net (code "34") (name "Net-(Q2-D)") (class "Default")
      (node (ref "JP1") (pin "2") (pinfunction "2_2") (pintype "passive"))
      (node (ref "Q2") (pin "3") (pinfunction "D_3") (pintype "passive"))
      (node (ref "R14") (pin "2") (pinfunction "2_2") (pintype "passive"))
    )
    (net (code "35") (name "Net-(Q3-D)") (class "Default")
      (node (ref "JP2") (pin "2") (pinfunction "2_2") (pintype "passive"))
      (node (ref "Q3") (pin "3") (pinfunction "D_3") (pintype "passive"))
      (node (ref "R16") (pin "2") (pinfunction "2_2") (pintype "passive"))
    )
    (net (code "36") (name "Net-(Q4-D)") (class "Default")
      (node (ref "D6") (pin "C") (pinfunction "C_C") (pintype "passive"))
      (node (ref "Q4") (pin "4") (pinfunction "D_4") (pintype "passive"))
      (node (ref "X1") (pin "1") (pinfunction "K_1") (pintype "passive"))
    )
    (net (code "37") (name "Net-(Q4-G)") (class "Default")
      (node (ref "C9") (pin "1") (pinfunction "1_1") (pintype "passive"))
      (node (ref "D2") (pin "A") (pinfunction "A_A") (pintype "passive"))
      (node (ref "Q4") (pin "1") (pinfunction "G_1") (pintype "passive"))
      (node (ref "R2") (pin "2") (pinfunction "2_2") (pintype "passive"))
    )
    (net (code "38") (name "Net-(Q10-D)") (class "Default")
      (node (ref "Q10") (pin "2") (pinfunction "D_2") (pintype "passive"))
      (node (ref "X3") (pin "2") (pinfunction "K_2") (pintype "passive"))
    )
    (net (code "39") (name "Net-(Q11-D)") (class "Default")
      (node (ref "Q11") (pin "2") (pinfunction "D_2") (pintype "passive"))
      (node (ref "X3") (pin "3") (pinfunction "K_3") (pintype "passive"))
    )
    (net (code "40") (name "Net-(Q12-D)") (class "Default")
      (node (ref "Q12") (pin "2") (pinfunction "D_2") (pintype "passive"))
      (node (ref "X3") (pin "4") (pinfunction "K_4") (pintype "passive"))
    )
    (net (code "41") (name "Net-(Q13-D)") (class "Default")
      (node (ref "Q13") (pin "2") (pinfunction "D_2") (pintype "passive"))
      (node (ref "X3") (pin "5") (pinfunction "K_5") (pintype "passive"))
    )
    (net (code "42") (name "Net-(U4-IN)") (class "Default")
      (node (ref "C11") (pin "+") (pinfunction "+_+") (pintype "passive"))
      (node (ref "D1") (pin "C") (pinfunction "C_C") (pintype "passive"))
      (node (ref "D5") (pin "C") (pinfunction "C_C") (pintype "passive"))
      (node (ref "U4") (pin "3") (pinfunction "IN_3") (pintype "input"))
    )
    (net (code "43") (name "Net-(X2B-K)") (class "Default")
      (node (ref "R21") (pin "2") (pinfunction "2_2") (pintype "passive"))
      (node (ref "R23") (pin "1") (pinfunction "1_1") (pintype "passive"))
      (node (ref "X2") (pin "2") (pinfunction "K_2") (pintype "passive"))
    )
    (net (code "44") (name "Net-(X2E-K)") (class "Default")
      (node (ref "R22") (pin "2") (pinfunction "2_2") (pintype "passive"))
      (node (ref "R24") (pin "1") (pinfunction "1_1") (pintype "passive"))
      (node (ref "X2") (pin "5") (pinfunction "K_5") (pintype "passive"))
    )
    (net (code "45") (name "PWM0") (class "Default")
      (node (ref "IC4") (pin "2") (pinfunction "IN1_2") (pintype "input"))
      (node (ref "R36") (pin "1") (pinfunction "1_1") (pintype "passive"))
      (node (ref "U1") (pin "29") (pinfunction "IO5_29") (pintype "bidirectional"))
    )
    (net (code "46") (name "PWM1") (class "Default")
      (node (ref "IC4") (pin "8") (pinfunction "EN2_8") (pintype "input"))
      (node (ref "R37") (pin "1") (pinfunction "1_1") (pintype "passive"))
      (node (ref "U1") (pin "30") (pinfunction "IO18_30") (pintype "bidirectional"))
    )
    (net (code "47") (name "PWM2") (class "Default")
      (node (ref "IC5") (pin "2") (pinfunction "IN1_2") (pintype "input"))
      (node (ref "R40") (pin "1") (pinfunction "1_1") (pintype "passive"))
      (node (ref "U1") (pin "31") (pinfunction "IO19_31") (pintype "bidirectional"))
    )
    (net (code "48") (name "PWM3") (class "Default")
      (node (ref "IC5") (pin "8") (pinfunction "EN2_8") (pintype "input"))
      (node (ref "R41") (pin "1") (pinfunction "1_1") (pintype "passive"))
      (node (ref "U1") (pin "33") (pinfunction "IO21_33") (pintype "bidirectional"))
    )
    (net (code "49") (name "unconnected-(D5-PadA)") (class "Default")
      (node (ref "D5") (pin "A") (pinfunction "A_A") (pintype "passive"))
    )
    (net (code "50") (name "unconnected-(J3-Pad10)") (class "Default")
      (node (ref "J3") (pin "10") (pinfunction "10_10") (pintype "passive"))
    )
    (net (code "51") (name "unconnected-(S1-P1-Pad2)") (class "Default")
      (node (ref "S1") (pin "2") (pinfunction "P1_2") (pintype "passive"))
    )
    (net (code "52") (name "unconnected-(S3-P1-Pad2)") (class "Default")
      (node (ref "S3") (pin "2") (pinfunction "P1_2") (pintype "passive"))
    )
    (net (code "53") (name "unconnected-(U1-CLK-Pad20)") (class "Default")
      (node (ref "U1") (pin "20") (pinfunction "CLK_20") (pintype "bidirectional"))
    )
    (net (code "54") (name "unconnected-(U1-CMD-Pad19)") (class "Default")
      (node (ref "U1") (pin "19") (pinfunction "CMD_19") (pintype "bidirectional"))
    )
    (net (code "55") (name "unconnected-(U1-IO2-Pad24)") (class "Default")
      (node (ref "U1") (pin "24") (pinfunction "IO2_24") (pintype "bidirectional"))
    )
    (net (code "56") (name "unconnected-(U1-IO4-Pad26)") (class "Default")
      (node (ref "U1") (pin "26") (pinfunction "IO4_26") (pintype "bidirectional"))
    )
    (net (code "57") (name "unconnected-(U1-IO32-Pad8)") (class "Default")
      (node (ref "U1") (pin "8") (pinfunction "IO32_8") (pintype "bidirectional"))
    )
    (net (code "58") (name "unconnected-(U1-IO33-Pad9)") (class "Default")
      (node (ref "U1") (pin "9") (pinfunction "IO33_9") (pintype "bidirectional"))
    )
    (net (code "59") (name "unconnected-(U1-IO35-Pad7)") (class "Default")
      (node (ref "U1") (pin "7") (pinfunction "IO35_7") (pintype "input"))
    )
    (net (code "60") (name "unconnected-(U1-NC-Pad32)") (class "Default")
      (node (ref "U1") (pin "32") (pinfunction "NC_32") (pintype "bidirectional"))
    )
    (net (code "61") (name "unconnected-(U1-PadGND)") (class "Default")
      (node (ref "U1") (pin "GND") (pinfunction "GND_GND") (pintype "bidirectional"))
    )
    (net (code "62") (name "unconnected-(U1-SD1-Pad22)") (class "Default")
      (node (ref "U1") (pin "22") (pinfunction "SD1_22") (pintype "bidirectional"))
    )
    (net (code "63") (name "unconnected-(U1-SD2-Pad17)") (class "Default")
      (node (ref "U1") (pin "17") (pinfunction "SD2_17") (pintype "bidirectional"))
    )
    (net (code "64") (name "unconnected-(U1-SD3-Pad18)") (class "Default")
      (node (ref "U1") (pin "18") (pinfunction "SD3_18") (pintype "bidirectional"))
    )
    (net (code "65") (name "unconnected-(U1-SDO-Pad21)") (class "Default")
      (node (ref "U1") (pin "21") (pinfunction "SDO_21") (pintype "bidirectional"))
    )
    (net (code "66") (name "unconnected-(U1-SENSOR_VN-Pad5)") (class "Default")
      (node (ref "U1") (pin "5") (pinfunction "SENSOR_VN_5") (pintype "input"))
    )
    (net (code "67") (name "unconnected-(U1-SENSOR_VP-Pad4)") (class "Default")
      (node (ref "U1") (pin "4") (pinfunction "SENSOR_VP_4") (pintype "input"))
    )
    (net (code "68") (name "unconnected-(U3-INT-Pad5)") (class "Default")
      (node (ref "U3") (pin "5") (pinfunction "INT_5") (pintype "output"))
    )
    (net (code "69") (name "unconnected-(U14-OS-Pad3)") (class "Default")
      (node (ref "U14") (pin "3") (pinfunction "OS_3") (pintype "output"))
    )
  )
)
